# Base_Board.net
KiCad netlist of a schematic drawn in EAGLE
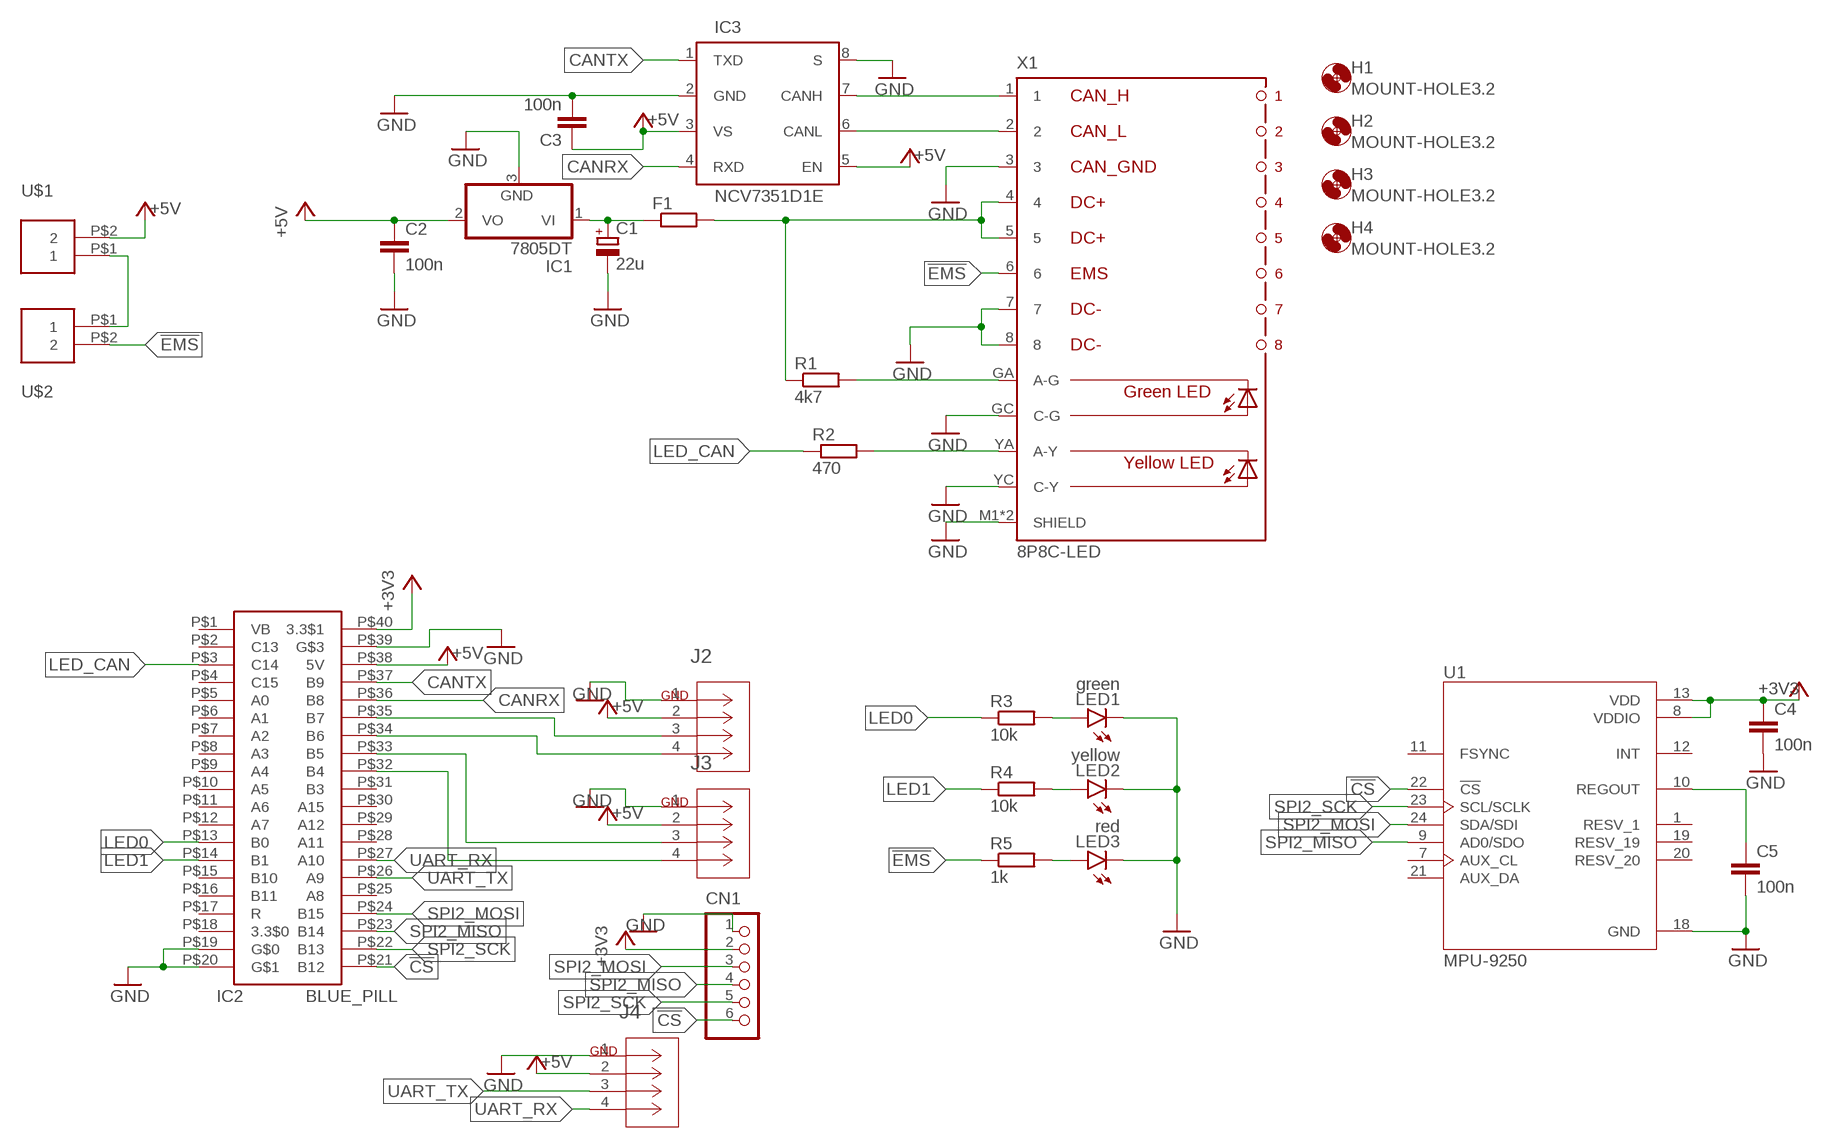
[diagram p0: schematic, sheet 1]

(export (version "E")
  (design (tool "Eeschema 10.0.6"))
  (components
    (comp (ref "C1")
      (value "22u")
      (footprint "eagle-import:E2,5-5")
      (libsource (lib "eagle-import") (part "CPOL-EUE2.5-5"))
    )
    (comp (ref "C2")
      (value "100n")
      (footprint "eagle-import:C0603")
      (libsource (lib "eagle-import") (part "C-EUC0603"))
    )
    (comp (ref "C3")
      (value "100n")
      (footprint "eagle-import:C0603")
      (libsource (lib "eagle-import") (part "C-EUC0603"))
    )
    (comp (ref "C4")
      (value "100n")
      (footprint "eagle-import:C0603")
      (libsource (lib "eagle-import") (part "C-EUC0603"))
    )
    (comp (ref "C5")
      (value "100n")
      (footprint "eagle-import:C0603")
      (libsource (lib "eagle-import") (part "C-EUC0603"))
    )
    (comp (ref "CN1")
      (value "S6B-XH-A")
      (footprint "eagle-import:S6B-XH-A")
      (libsource (lib "eagle-import") (part "S6B-XH-A"))
    )
    (comp (ref "F1")
      (value "R-EU_R1206")
      (footprint "eagle-import:R1206")
      (libsource (lib "eagle-import") (part "R-EU_R1206"))
    )
    (comp (ref "H1")
      (value "MOUNT-HOLE3.2")
      (footprint "eagle-import:3,2")
      (libsource (lib "eagle-import") (part "MOUNT-HOLE3.2"))
    )
    (comp (ref "H2")
      (value "MOUNT-HOLE3.2")
      (footprint "eagle-import:3,2")
      (libsource (lib "eagle-import") (part "MOUNT-HOLE3.2"))
    )
    (comp (ref "H3")
      (value "MOUNT-HOLE3.2")
      (footprint "eagle-import:3,2")
      (libsource (lib "eagle-import") (part "MOUNT-HOLE3.2"))
    )
    (comp (ref "H4")
      (value "MOUNT-HOLE3.2")
      (footprint "eagle-import:3,2")
      (libsource (lib "eagle-import") (part "MOUNT-HOLE3.2"))
    )
    (comp (ref "IC1")
      (value "7805DT")
      (footprint "eagle-import:TO252")
      (libsource (lib "eagle-import") (part "78DT05"))
    )
    (comp (ref "IC2")
      (value "BLUE_PILL")
      (footprint "eagle-import:BLUE_PILL")
      (libsource (lib "eagle-import") (part "BLUE_PILL"))
    )
    (comp (ref "IC3")
      (value "NCV7351D1E")
      (footprint "eagle-import:SO08")
      (libsource (lib "eagle-import") (part "NCV7351D1E"))
    )
    (comp (ref "J2")
      (value "EP2.5-4-SIDE")
      (footprint "eagle-import:CONN4_1744426-4")
      (fields (field (name "MANUFACTURER_PART_NUMBER") "17444264"))
      (libsource (lib "eagle-import") (part "EP2.5-4-SIDE"))
    )
    (comp (ref "J3")
      (value "EP2.5-4-SIDE")
      (footprint "eagle-import:CONN4_1744426-4")
      (fields (field (name "MANUFACTURER_PART_NUMBER") "17444264"))
      (libsource (lib "eagle-import") (part "EP2.5-4-SIDE"))
    )
    (comp (ref "J4")
      (value "EP2.5-4-SIDE")
      (footprint "eagle-import:CONN4_1744426-4")
      (fields (field (name "MANUFACTURER_PART_NUMBER") "17444264"))
      (libsource (lib "eagle-import") (part "EP2.5-4-SIDE"))
    )
    (comp (ref "LED1")
      (value "green")
      (footprint "eagle-import:CHIPLED_0805")
      (libsource (lib "eagle-import") (part "LEDCHIPLED_0805"))
    )
    (comp (ref "LED2")
      (value "yellow")
      (footprint "eagle-import:CHIPLED_0805")
      (libsource (lib "eagle-import") (part "LEDCHIPLED_0805"))
    )
    (comp (ref "LED3")
      (value "red")
      (footprint "eagle-import:CHIPLED_0805")
      (libsource (lib "eagle-import") (part "LEDCHIPLED_0805"))
    )
    (comp (ref "R1")
      (value "4k7")
      (footprint "eagle-import:R0603")
      (libsource (lib "eagle-import") (part "R-EU_R0603"))
    )
    (comp (ref "R2")
      (value "470")
      (footprint "eagle-import:R0603")
      (libsource (lib "eagle-import") (part "R-EU_R0603"))
    )
    (comp (ref "R3")
      (value "10k")
      (footprint "eagle-import:R0603")
      (libsource (lib "eagle-import") (part "R-EU_R0603"))
    )
    (comp (ref "R4")
      (value "10k")
      (footprint "eagle-import:R0603")
      (libsource (lib "eagle-import") (part "R-EU_R0603"))
    )
    (comp (ref "R5")
      (value "1k")
      (footprint "eagle-import:R0603")
      (libsource (lib "eagle-import") (part "R-EU_R0603"))
    )
    (comp (ref "U$1")
      (value "XH-2-STRAIGHT")
      (footprint "eagle-import:CON-XH-2-STRAIGHT")
      (libsource (lib "eagle-import") (part "XH-2-STRAIGHT"))
    )
    (comp (ref "U$2")
      (value "XH-2-STRAIGHT")
      (footprint "eagle-import:CON-XH-2-STRAIGHT")
      (libsource (lib "eagle-import") (part "XH-2-STRAIGHT"))
    )
    (comp (ref "U1")
      (value "MPU-9250")
      (footprint "eagle-import:QFN40P300X300X105-24N")
      (fields (field (name "MF") "TDK InvenSense"))
      (libsource (lib "eagle-import") (part "MPU-9250"))
    )
    (comp (ref "X1")
      (value "8P8C-LED")
      (footprint "eagle-import:8P8C-LED")
      (libsource (lib "eagle-import") (part "8P8C-LED"))
    )
  )
  (nets
    (net (code "1") (name "+3V3") (class "Default")
      (node (ref "C4") (pin "1") (pinfunction "1_1") (pintype "passive"))
      (node (ref "CN1") (pin "2") (pinfunction "2_2") (pintype "passive"))
      (node (ref "IC2") (pin "P$40") (pinfunction "3.3$1_P$40") (pintype "passive"))
      (node (ref "U1") (pin "13") (pinfunction "VDD_13") (pintype "power_in"))
      (node (ref "U1") (pin "8") (pinfunction "VDDIO_8") (pintype "power_in"))
    )
    (net (code "2") (name "+5V") (class "Default")
      (node (ref "C2") (pin "1") (pinfunction "1_1") (pintype "passive"))
      (node (ref "C3") (pin "1") (pinfunction "1_1") (pintype "passive"))
      (node (ref "IC1") (pin "2") (pinfunction "VO_2") (pintype "passive"))
      (node (ref "IC2") (pin "P$38") (pinfunction "5V_P$38") (pintype "bidirectional"))
      (node (ref "IC3") (pin "3") (pinfunction "VS_3") (pintype "power_in"))
      (node (ref "IC3") (pin "5") (pinfunction "EN_5") (pintype "input"))
      (node (ref "J2") (pin "2") (pinfunction "2_2") (pintype "passive"))
      (node (ref "J3") (pin "2") (pinfunction "2_2") (pintype "passive"))
      (node (ref "J4") (pin "2") (pinfunction "2_2") (pintype "passive"))
      (node (ref "U$1") (pin "P$2") (pinfunction "2_P$2") (pintype "bidirectional"))
    )
    (net (code "3") (name "CANRX") (class "Default")
      (node (ref "IC2") (pin "P$36") (pinfunction "B8_P$36") (pintype "bidirectional"))
      (node (ref "IC3") (pin "4") (pinfunction "RXD_4") (pintype "output"))
    )
    (net (code "4") (name "CANTX") (class "Default")
      (node (ref "IC2") (pin "P$37") (pinfunction "B9_P$37") (pintype "bidirectional"))
      (node (ref "IC3") (pin "1") (pinfunction "TXD_1") (pintype "input"))
    )
    (net (code "5") (name "GND") (class "Default")
      (node (ref "C1") (pin "-") (pinfunction "-_-") (pintype "passive"))
      (node (ref "C2") (pin "2") (pinfunction "2_2") (pintype "passive"))
      (node (ref "C3") (pin "2") (pinfunction "2_2") (pintype "passive"))
      (node (ref "C4") (pin "2") (pinfunction "2_2") (pintype "passive"))
      (node (ref "C5") (pin "2") (pinfunction "2_2") (pintype "passive"))
      (node (ref "CN1") (pin "1") (pinfunction "1_1") (pintype "passive"))
      (node (ref "IC1") (pin "3") (pinfunction "GND_3") (pintype "passive"))
      (node (ref "IC2") (pin "P$19") (pinfunction "G$0_P$19") (pintype "passive"))
      (node (ref "IC2") (pin "P$20") (pinfunction "G$1_P$20") (pintype "passive"))
      (node (ref "IC2") (pin "P$39") (pinfunction "G$3_P$39") (pintype "passive"))
      (node (ref "IC3") (pin "2") (pinfunction "GND_2") (pintype "power_in"))
      (node (ref "IC3") (pin "8") (pinfunction "S_8") (pintype "input"))
      (node (ref "J2") (pin "1") (pinfunction "1_1") (pintype "passive"))
      (node (ref "J3") (pin "1") (pinfunction "1_1") (pintype "passive"))
      (node (ref "J4") (pin "1") (pinfunction "1_1") (pintype "passive"))
      (node (ref "LED1") (pin "C") (pinfunction "C_C") (pintype "passive"))
      (node (ref "LED2") (pin "C") (pinfunction "C_C") (pintype "passive"))
      (node (ref "LED3") (pin "C") (pinfunction "C_C") (pintype "passive"))
      (node (ref "U1") (pin "18") (pinfunction "GND_18") (pintype "power_in"))
      (node (ref "X1") (pin "3") (pinfunction "3_3") (pintype "input"))
      (node (ref "X1") (pin "7") (pinfunction "7_7") (pintype "input"))
      (node (ref "X1") (pin "8") (pinfunction "8_8") (pintype "input"))
      (node (ref "X1") (pin "GC") (pinfunction "C-G_GC") (pintype "passive"))
      (node (ref "X1") (pin "M1") (pinfunction "SHIELD_M1") (pintype "passive"))
      (node (ref "X1") (pin "M2") (pinfunction "SHIELD_M2") (pintype "passive"))
      (node (ref "X1") (pin "YC") (pinfunction "C-Y_YC") (pintype "passive"))
    )
    (net (code "6") (name "LED0") (class "Default")
      (node (ref "IC2") (pin "P$13") (pinfunction "B0_P$13") (pintype "bidirectional"))
      (node (ref "R3") (pin "1") (pinfunction "1_1") (pintype "passive"))
    )
    (net (code "7") (name "LED1") (class "Default")
      (node (ref "IC2") (pin "P$14") (pinfunction "B1_P$14") (pintype "bidirectional"))
      (node (ref "R4") (pin "1") (pinfunction "1_1") (pintype "passive"))
    )
    (net (code "8") (name "LED_CAN") (class "Default")
      (node (ref "IC2") (pin "P$3") (pinfunction "C14_P$3") (pintype "bidirectional"))
      (node (ref "R2") (pin "1") (pinfunction "1_1") (pintype "passive"))
    )
    (net (code "9") (name "Net-(F1-Pad2)") (class "Default")
      (node (ref "F1") (pin "2") (pinfunction "2_2") (pintype "passive"))
      (node (ref "R1") (pin "1") (pinfunction "1_1") (pintype "passive"))
      (node (ref "X1") (pin "4") (pinfunction "4_4") (pintype "input"))
      (node (ref "X1") (pin "5") (pinfunction "5_5") (pintype "input"))
    )
    (net (code "10") (name "Net-(IC1-VI)") (class "Default")
      (node (ref "C1") (pin "+") (pinfunction "+_+") (pintype "passive"))
      (node (ref "F1") (pin "1") (pinfunction "1_1") (pintype "passive"))
      (node (ref "IC1") (pin "1") (pinfunction "VI_1") (pintype "input"))
    )
    (net (code "11") (name "Net-(IC2-B4)") (class "Default")
      (node (ref "IC2") (pin "P$32") (pinfunction "B4_P$32") (pintype "bidirectional"))
      (node (ref "J3") (pin "4") (pinfunction "4_4") (pintype "passive"))
    )
    (net (code "12") (name "Net-(IC2-B5)") (class "Default")
      (node (ref "IC2") (pin "P$33") (pinfunction "B5_P$33") (pintype "bidirectional"))
      (node (ref "J3") (pin "3") (pinfunction "3_3") (pintype "passive"))
    )
    (net (code "13") (name "Net-(IC2-B6)") (class "Default")
      (node (ref "IC2") (pin "P$34") (pinfunction "B6_P$34") (pintype "bidirectional"))
      (node (ref "J2") (pin "4") (pinfunction "4_4") (pintype "passive"))
    )
    (net (code "14") (name "Net-(IC2-B7)") (class "Default")
      (node (ref "IC2") (pin "P$35") (pinfunction "B7_P$35") (pintype "bidirectional"))
      (node (ref "J2") (pin "3") (pinfunction "3_3") (pintype "passive"))
    )
    (net (code "15") (name "Net-(IC3-CANH)") (class "Default")
      (node (ref "IC3") (pin "7") (pinfunction "CANH_7") (pintype "output"))
      (node (ref "X1") (pin "1") (pinfunction "1_1") (pintype "input"))
    )
    (net (code "16") (name "Net-(IC3-CANL)") (class "Default")
      (node (ref "IC3") (pin "6") (pinfunction "CANL_6") (pintype "output"))
      (node (ref "X1") (pin "2") (pinfunction "2_2") (pintype "input"))
    )
    (net (code "17") (name "Net-(LED1-PadA)") (class "Default")
      (node (ref "LED1") (pin "A") (pinfunction "A_A") (pintype "passive"))
      (node (ref "R3") (pin "2") (pinfunction "2_2") (pintype "passive"))
    )
    (net (code "18") (name "Net-(LED2-PadA)") (class "Default")
      (node (ref "LED2") (pin "A") (pinfunction "A_A") (pintype "passive"))
      (node (ref "R4") (pin "2") (pinfunction "2_2") (pintype "passive"))
    )
    (net (code "19") (name "Net-(LED3-PadA)") (class "Default")
      (node (ref "LED3") (pin "A") (pinfunction "A_A") (pintype "passive"))
      (node (ref "R5") (pin "2") (pinfunction "2_2") (pintype "passive"))
    )
    (net (code "20") (name "Net-(U$1-1)") (class "Default")
      (node (ref "U$1") (pin "P$1") (pinfunction "1_P$1") (pintype "bidirectional"))
      (node (ref "U$2") (pin "P$1") (pinfunction "1_P$1") (pintype "bidirectional"))
    )
    (net (code "21") (name "Net-(U1-REGOUT)") (class "Default")
      (node (ref "C5") (pin "1") (pinfunction "1_1") (pintype "passive"))
      (node (ref "U1") (pin "10") (pinfunction "REGOUT_10") (pintype "output"))
    )
    (net (code "22") (name "Net-(X1-A-G)") (class "Default")
      (node (ref "R1") (pin "2") (pinfunction "2_2") (pintype "passive"))
      (node (ref "X1") (pin "GA") (pinfunction "A-G_GA") (pintype "passive"))
    )
    (net (code "23") (name "Net-(X1-A-Y)") (class "Default")
      (node (ref "R2") (pin "2") (pinfunction "2_2") (pintype "passive"))
      (node (ref "X1") (pin "YA") (pinfunction "A-Y_YA") (pintype "passive"))
    )
    (net (code "24") (name "SPI2_MISO") (class "Default")
      (node (ref "CN1") (pin "4") (pinfunction "4_4") (pintype "passive"))
      (node (ref "IC2") (pin "P$23") (pinfunction "B14_P$23") (pintype "bidirectional"))
      (node (ref "U1") (pin "9") (pinfunction "AD0/SDO_9") (pintype "output"))
    )
    (net (code "25") (name "SPI2_MOSI") (class "Default")
      (node (ref "CN1") (pin "3") (pinfunction "3_3") (pintype "passive"))
      (node (ref "IC2") (pin "P$24") (pinfunction "B15_P$24") (pintype "bidirectional"))
      (node (ref "U1") (pin "24") (pinfunction "SDA/SDI_24") (pintype "bidirectional"))
    )
    (net (code "26") (name "SPI2_SCK") (class "Default")
      (node (ref "CN1") (pin "5") (pinfunction "5_5") (pintype "passive"))
      (node (ref "IC2") (pin "P$22") (pinfunction "B13_P$22") (pintype "bidirectional"))
      (node (ref "U1") (pin "23") (pinfunction "SCL/SCLK_23") (pintype "input"))
    )
    (net (code "27") (name "UART_RX") (class "Default")
      (node (ref "IC2") (pin "P$27") (pinfunction "A10_P$27") (pintype "bidirectional"))
      (node (ref "J4") (pin "4") (pinfunction "4_4") (pintype "passive"))
    )
    (net (code "28") (name "UART_TX") (class "Default")
      (node (ref "IC2") (pin "P$26") (pinfunction "A9_P$26") (pintype "bidirectional"))
      (node (ref "J4") (pin "3") (pinfunction "3_3") (pintype "passive"))
    )
    (net (code "29") (name "unconnected-(IC2-3.3$0-PadP$18)") (class "Default")
      (node (ref "IC2") (pin "P$18") (pinfunction "3.3$0_P$18") (pintype "passive"))
    )
    (net (code "30") (name "unconnected-(IC2-A0-PadP$5)") (class "Default")
      (node (ref "IC2") (pin "P$5") (pinfunction "A0_P$5") (pintype "bidirectional"))
    )
    (net (code "31") (name "unconnected-(IC2-A1-PadP$6)") (class "Default")
      (node (ref "IC2") (pin "P$6") (pinfunction "A1_P$6") (pintype "bidirectional"))
    )
    (net (code "32") (name "unconnected-(IC2-A2-PadP$7)") (class "Default")
      (node (ref "IC2") (pin "P$7") (pinfunction "A2_P$7") (pintype "bidirectional"))
    )
    (net (code "33") (name "unconnected-(IC2-A3-PadP$8)") (class "Default")
      (node (ref "IC2") (pin "P$8") (pinfunction "A3_P$8") (pintype "bidirectional"))
    )
    (net (code "34") (name "unconnected-(IC2-A4-PadP$9)") (class "Default")
      (node (ref "IC2") (pin "P$9") (pinfunction "A4_P$9") (pintype "bidirectional"))
    )
    (net (code "35") (name "unconnected-(IC2-A5-PadP$10)") (class "Default")
      (node (ref "IC2") (pin "P$10") (pinfunction "A5_P$10") (pintype "bidirectional"))
    )
    (net (code "36") (name "unconnected-(IC2-A6-PadP$11)") (class "Default")
      (node (ref "IC2") (pin "P$11") (pinfunction "A6_P$11") (pintype "bidirectional"))
    )
    (net (code "37") (name "unconnected-(IC2-A7-PadP$12)") (class "Default")
      (node (ref "IC2") (pin "P$12") (pinfunction "A7_P$12") (pintype "bidirectional"))
    )
    (net (code "38") (name "unconnected-(IC2-A8-PadP$25)") (class "Default")
      (node (ref "IC2") (pin "P$25") (pinfunction "A8_P$25") (pintype "bidirectional"))
    )
    (net (code "39") (name "unconnected-(IC2-A11-PadP$28)") (class "Default")
      (node (ref "IC2") (pin "P$28") (pinfunction "A11_P$28") (pintype "bidirectional"))
    )
    (net (code "40") (name "unconnected-(IC2-A12-PadP$29)") (class "Default")
      (node (ref "IC2") (pin "P$29") (pinfunction "A12_P$29") (pintype "bidirectional"))
    )
    (net (code "41") (name "unconnected-(IC2-A15-PadP$30)") (class "Default")
      (node (ref "IC2") (pin "P$30") (pinfunction "A15_P$30") (pintype "bidirectional"))
    )
    (net (code "42") (name "unconnected-(IC2-B3-PadP$31)") (class "Default")
      (node (ref "IC2") (pin "P$31") (pinfunction "B3_P$31") (pintype "bidirectional"))
    )
    (net (code "43") (name "unconnected-(IC2-B10-PadP$15)") (class "Default")
      (node (ref "IC2") (pin "P$15") (pinfunction "B10_P$15") (pintype "bidirectional"))
    )
    (net (code "44") (name "unconnected-(IC2-B11-PadP$16)") (class "Default")
      (node (ref "IC2") (pin "P$16") (pinfunction "B11_P$16") (pintype "bidirectional"))
    )
    (net (code "45") (name "unconnected-(IC2-C13-PadP$2)") (class "Default")
      (node (ref "IC2") (pin "P$2") (pinfunction "C13_P$2") (pintype "bidirectional"))
    )
    (net (code "46") (name "unconnected-(IC2-C15-PadP$4)") (class "Default")
      (node (ref "IC2") (pin "P$4") (pinfunction "C15_P$4") (pintype "bidirectional"))
    )
    (net (code "47") (name "unconnected-(IC2-R-PadP$17)") (class "Default")
      (node (ref "IC2") (pin "P$17") (pinfunction "R_P$17") (pintype "bidirectional"))
    )
    (net (code "48") (name "unconnected-(IC2-VB-PadP$1)") (class "Default")
      (node (ref "IC2") (pin "P$1") (pinfunction "VB_P$1") (pintype "bidirectional"))
    )
    (net (code "49") (name "unconnected-(U1-AUX_CL-Pad7)") (class "Default")
      (node (ref "U1") (pin "7") (pinfunction "AUX_CL_7") (pintype "input"))
    )
    (net (code "50") (name "unconnected-(U1-AUX_DA-Pad21)") (class "Default")
      (node (ref "U1") (pin "21") (pinfunction "AUX_DA_21") (pintype "input"))
    )
    (net (code "51") (name "unconnected-(U1-FSYNC-Pad11)") (class "Default")
      (node (ref "U1") (pin "11") (pinfunction "FSYNC_11") (pintype "input"))
    )
    (net (code "52") (name "unconnected-(U1-INT-Pad12)") (class "Default")
      (node (ref "U1") (pin "12") (pinfunction "INT_12") (pintype "output"))
    )
    (net (code "53") (name "unconnected-(U1-RESV_1-Pad1)") (class "Default")
      (node (ref "U1") (pin "1") (pinfunction "RESV_1_1") (pintype "passive"))
    )
    (net (code "54") (name "unconnected-(U1-RESV_19-Pad19)") (class "Default")
      (node (ref "U1") (pin "19") (pinfunction "RESV_19_19") (pintype "passive"))
    )
    (net (code "55") (name "unconnected-(U1-RESV_20-Pad20)") (class "Default")
      (node (ref "U1") (pin "20") (pinfunction "RESV_20_20") (pintype "passive"))
    )
    (net (code "56") (name "~{CS}") (class "Default")
      (node (ref "CN1") (pin "6") (pinfunction "6_6") (pintype "passive"))
      (node (ref "IC2") (pin "P$21") (pinfunction "B12_P$21") (pintype "bidirectional"))
      (node (ref "U1") (pin "22") (pinfunction "~{CS}_22") (pintype "input"))
    )
    (net (code "57") (name "~{EMS}") (class "Default")
      (node (ref "R5") (pin "1") (pinfunction "1_1") (pintype "passive"))
      (node (ref "U$2") (pin "P$2") (pinfunction "2_P$2") (pintype "bidirectional"))
      (node (ref "X1") (pin "6") (pinfunction "6_6") (pintype "input"))
    )
  )
)
